# WirelessMonitorSch.net
KiCad netlist of a schematic drawn in Altium Designer
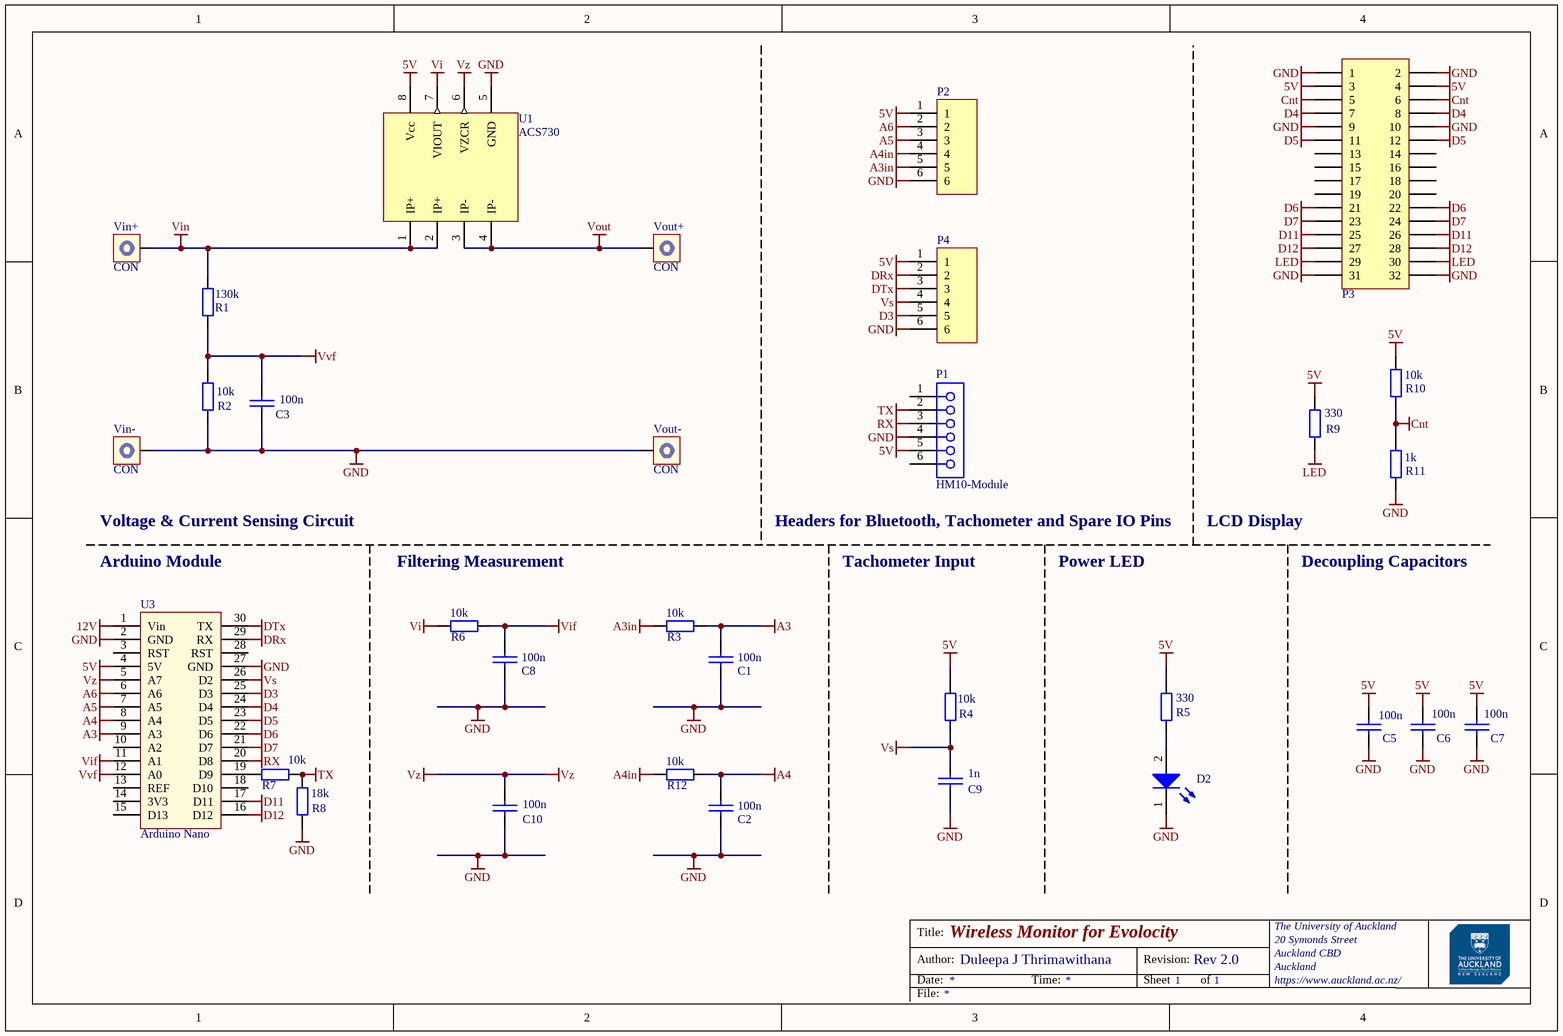
[diagram p0: WirelessMonitorSch.SchDoc]

(export (version "E")
  (design (tool "Eeschema 10.0.6"))
  (components
    (comp (ref "C1")
      (value "100n")
      (footprint "C0805")
      (description "CCAP0805")
      (fields (field (name "LCSC PART NUMBER") "C49678"))
      (libsource (lib "CommonDevices_V1") (part "CCAP0805"))
    )
    (comp (ref "C2")
      (value "100n")
      (footprint "C0805")
      (description "CCAP0805")
      (fields (field (name "LCSC PART NUMBER") "C49678"))
      (libsource (lib "CommonDevices_V1") (part "CCAP0805"))
    )
    (comp (ref "C3")
      (value "100n")
      (footprint "C0805")
      (description "CCAP0805")
      (fields (field (name "LCSC PART NUMBER") "C49678"))
      (libsource (lib "CommonDevices_V1") (part "CCAP0805"))
    )
    (comp (ref "C5")
      (value "100n")
      (footprint "C0805")
      (description "CCAP0805")
      (fields (field (name "LCSC PART NUMBER") "C49678"))
      (libsource (lib "CommonDevices_V1") (part "CCAP0805"))
    )
    (comp (ref "C6")
      (value "100n")
      (footprint "C0805")
      (description "CCAP0805")
      (fields (field (name "LCSC PART NUMBER") "C49678"))
      (libsource (lib "CommonDevices_V1") (part "CCAP0805"))
    )
    (comp (ref "C7")
      (value "100n")
      (footprint "C0805")
      (description "CCAP0805")
      (fields (field (name "LCSC PART NUMBER") "C49678"))
      (libsource (lib "CommonDevices_V1") (part "CCAP0805"))
    )
    (comp (ref "C8")
      (value "100n")
      (footprint "C0805")
      (description "CCAP0805")
      (fields (field (name "LCSC PART NUMBER") "C49678"))
      (libsource (lib "CommonDevices_V1") (part "CCAP0805"))
    )
    (comp (ref "C9")
      (value "1n")
      (footprint "C0805")
      (description "CCAP0805")
      (fields (field (name "LCSC PART NUMBER") "C46653"))
      (libsource (lib "CommonDevices_V1") (part "CCAP0805"))
    )
    (comp (ref "C10")
      (value "100n")
      (footprint "C0805")
      (description "CCAP0805")
      (fields (field (name "LCSC PART NUMBER") "C49678"))
      (libsource (lib "CommonDevices_V1") (part "CCAP0805"))
    )
    (comp (ref "D2")
      (value "LGR971-KN-1")
      (footprint "FP-LG_R971-MFG")
      (description "LED Uni-Color Green 572nm 2-Pin SMD T/R")
      (fields (field (name "LCSC PART NUMBER") "C2297"))
      (libsource (lib "ECSE@UoA") (part "8706943c75ba83719d021d2fdc84c58"))
    )
    (comp (ref "P1")
      (value "HM10-Module")
      (footprint "SMTC-SSW-106-02-X-S")
      (description "CONN RCPT 6POS 0.1 TIN PCB")
      (libsource (lib "ECSE@UoA") (part "SMTC-SSW-106-02-X-S-X"))
    )
    (comp (ref "P2")
      (value "Header 6X1")
      (footprint "HDR6X1_2P54")
      (description "Header, 6-Pin")
      (fields (field (name "PUBLISHER") "Altium Limited"))
      (libsource (lib "CommonDevices_V1") (part "HDR6X1"))
    )
    (comp (ref "P3")
      (value "HDR16X2")
      (footprint "HDR16X2_2P54")
      (description "Header, 16-Pin, Dual row")
      (libsource (lib "CommonDevices_V1") (part "HDR16X2"))
    )
    (comp (ref "P4")
      (value "Header 6X1")
      (footprint "HDR6X1_2P54")
      (description "Header, 6-Pin")
      (fields (field (name "PUBLISHER") "Altium Limited"))
      (libsource (lib "CommonDevices_V1") (part "HDR6X1"))
    )
    (comp (ref "R1")
      (value "130k")
      (footprint "R0805")
      (description "RES0805")
      (fields (field (name "LCSC PART NUMBER") "C25617"))
      (libsource (lib "") (part "RES0805_1"))
    )
    (comp (ref "R2")
      (value "10k")
      (footprint "R0805")
      (description "RES0805")
      (fields (field (name "LCSC PART NUMBER") "C17414"))
      (libsource (lib "") (part "RES0805_1"))
    )
    (comp (ref "R3")
      (value "10k")
      (footprint "R0805")
      (description "RES0805")
      (fields (field (name "LCSC PART NUMBER") "C17414"))
      (libsource (lib "CommonDevices_V1") (part "RES0805"))
    )
    (comp (ref "R4")
      (value "10k")
      (footprint "R0805")
      (description "RES0805")
      (fields (field (name "LCSC PART NUMBER") "C17414"))
      (libsource (lib "") (part "RES0805_1"))
    )
    (comp (ref "R5")
      (value "330")
      (footprint "R0805")
      (description "RES0805")
      (fields (field (name "LCSC PART NUMBER") "C17630"))
      (libsource (lib "") (part "RES0805_1"))
    )
    (comp (ref "R6")
      (value "10k")
      (footprint "R0805")
      (description "RES0805")
      (fields (field (name "LCSC PART NUMBER") "C17414"))
      (libsource (lib "CommonDevices_V1") (part "RES0805"))
    )
    (comp (ref "R7")
      (value "10k")
      (footprint "R0805")
      (description "RES0805")
      (fields (field (name "LCSC PART NUMBER") "C17414"))
      (libsource (lib "CommonDevices_V1") (part "RES0805"))
    )
    (comp (ref "R8")
      (value "18k")
      (footprint "R0805")
      (description "RES0805")
      (fields (field (name "LCSC PART NUMBER") "C17506"))
      (libsource (lib "") (part "RES0805_1"))
    )
    (comp (ref "R9")
      (value "330")
      (footprint "R0805")
      (description "RES0805")
      (fields (field (name "LCSC PART NUMBER") "C17630"))
      (libsource (lib "") (part "RES0805_1"))
    )
    (comp (ref "R10")
      (value "10k")
      (footprint "R0805")
      (description "RES0805")
      (fields (field (name "LCSC PART NUMBER") "C17414"))
      (libsource (lib "") (part "RES0805_1"))
    )
    (comp (ref "R11")
      (value "1k")
      (footprint "R0805")
      (description "RES0805")
      (fields (field (name "LCSC PART NUMBER") "C17513"))
      (libsource (lib "") (part "RES0805_1"))
    )
    (comp (ref "R12")
      (value "10k")
      (footprint "R0805")
      (description "RES0805")
      (fields (field (name "LCSC PART NUMBER") "C17414"))
      (libsource (lib "CommonDevices_V1") (part "RES0805"))
    )
    (comp (ref "U1")
      (value "ACS730")
      (footprint "SOIC8")
      (libsource (lib "CommonDevices_V1") (part "ACS730"))
    )
    (comp (ref "U3")
      (value "Arduino Nano")
      (footprint "ArduinoNanoSMT")
      (libsource (lib "CommonDevices_V1") (part "ArduinoNano"))
    )
    (comp (ref "Vin+")
      (value "CON")
      (footprint "CON_M3")
      (description "Term")
      (fields (field (name "PART NUMBER") "74651194R") (field (name "PUBLISHER") "Wurth Elektronik"))
      (libsource (lib "") (part "Connector_1"))
    )
    (comp (ref "Vin-")
      (value "CON")
      (footprint "CON_M3")
      (description "Term")
      (fields (field (name "PART NUMBER") "74651194R") (field (name "PUBLISHER") "Wurth Elektronik"))
      (libsource (lib "") (part "Connector_1"))
    )
    (comp (ref "Vout+")
      (value "CON")
      (footprint "CON_M3")
      (description "Term")
      (fields (field (name "PART NUMBER") "74651194R") (field (name "PUBLISHER") "Wurth Elektronik"))
      (libsource (lib "CommonDevices_V1") (part "Connector"))
    )
    (comp (ref "Vout-")
      (value "CON")
      (footprint "CON_M3")
      (description "Term")
      (fields (field (name "PART NUMBER") "74651194R") (field (name "PUBLISHER") "Wurth Elektronik"))
      (libsource (lib "CommonDevices_V1") (part "Connector"))
    )
  )
  (nets
    (net (code "1") (name "5V") (class "Default")
      (node (ref "C5") (pin "2") (pinfunction "2_2") (pintype "passive"))
      (node (ref "C6") (pin "2") (pinfunction "2_2") (pintype "passive"))
      (node (ref "C7") (pin "2") (pinfunction "2_2") (pintype "passive"))
      (node (ref "P1") (pin "5") (pinfunction "5_5") (pintype "passive"))
      (node (ref "P2") (pin "1") (pinfunction "1_1") (pintype "passive"))
      (node (ref "P3") (pin "3") (pinfunction "3_3") (pintype "passive"))
      (node (ref "P3") (pin "4") (pinfunction "4_4") (pintype "passive"))
      (node (ref "P4") (pin "1") (pinfunction "1_1") (pintype "passive"))
      (node (ref "R10") (pin "2") (pinfunction "2_2") (pintype "passive"))
      (node (ref "R4") (pin "2") (pinfunction "2_2") (pintype "passive"))
      (node (ref "R5") (pin "2") (pinfunction "2_2") (pintype "passive"))
      (node (ref "R9") (pin "2") (pinfunction "2_2") (pintype "passive"))
      (node (ref "U1") (pin "8") (pinfunction "Vcc_8") (pintype "power_in"))
      (node (ref "U3") (pin "4") (pinfunction "5V_4") (pintype "passive"))
    )
    (net (code "2") (name "12V") (class "Default")
      (node (ref "U3") (pin "1") (pinfunction "Vin_1") (pintype "passive"))
    )
    (net (code "3") (name "A3") (class "Default")
      (node (ref "C1") (pin "2") (pinfunction "2_2") (pintype "passive"))
      (node (ref "R3") (pin "1") (pinfunction "1_1") (pintype "passive"))
      (node (ref "U3") (pin "9") (pinfunction "A3_9") (pintype "passive"))
    )
    (net (code "4") (name "A3in") (class "Default")
      (node (ref "P2") (pin "5") (pinfunction "5_5") (pintype "passive"))
      (node (ref "R3") (pin "2") (pinfunction "2_2") (pintype "passive"))
    )
    (net (code "5") (name "A4") (class "Default")
      (node (ref "C2") (pin "2") (pinfunction "2_2") (pintype "passive"))
      (node (ref "R12") (pin "1") (pinfunction "1_1") (pintype "passive"))
      (node (ref "U3") (pin "8") (pinfunction "A4_8") (pintype "passive"))
    )
    (net (code "6") (name "A4in") (class "Default")
      (node (ref "P2") (pin "4") (pinfunction "4_4") (pintype "passive"))
      (node (ref "R12") (pin "2") (pinfunction "2_2") (pintype "passive"))
    )
    (net (code "7") (name "A5") (class "Default")
      (node (ref "P2") (pin "3") (pinfunction "3_3") (pintype "passive"))
      (node (ref "U3") (pin "7") (pinfunction "A5_7") (pintype "passive"))
    )
    (net (code "8") (name "A6") (class "Default")
      (node (ref "P2") (pin "2") (pinfunction "2_2") (pintype "passive"))
      (node (ref "U3") (pin "6") (pinfunction "A6_6") (pintype "passive"))
    )
    (net (code "9") (name "Cnt") (class "Default")
      (node (ref "P3") (pin "5") (pinfunction "5_5") (pintype "passive"))
      (node (ref "P3") (pin "6") (pinfunction "6_6") (pintype "passive"))
      (node (ref "R10") (pin "1") (pinfunction "1_1") (pintype "passive"))
      (node (ref "R11") (pin "2") (pinfunction "2_2") (pintype "passive"))
    )
    (net (code "10") (name "D3") (class "Default")
      (node (ref "P4") (pin "5") (pinfunction "5_5") (pintype "passive"))
      (node (ref "U3") (pin "25") (pinfunction "D3_25") (pintype "passive"))
    )
    (net (code "11") (name "D4") (class "Default")
      (node (ref "P3") (pin "7") (pinfunction "7_7") (pintype "passive"))
      (node (ref "P3") (pin "8") (pinfunction "8_8") (pintype "passive"))
      (node (ref "U3") (pin "24") (pinfunction "D4_24") (pintype "passive"))
    )
    (net (code "12") (name "D5") (class "Default")
      (node (ref "P3") (pin "11") (pinfunction "11_11") (pintype "passive"))
      (node (ref "P3") (pin "12") (pinfunction "12_12") (pintype "passive"))
      (node (ref "U3") (pin "23") (pinfunction "D5_23") (pintype "passive"))
    )
    (net (code "13") (name "D6") (class "Default")
      (node (ref "P3") (pin "21") (pinfunction "21_21") (pintype "passive"))
      (node (ref "P3") (pin "22") (pinfunction "22_22") (pintype "passive"))
      (node (ref "U3") (pin "22") (pinfunction "D6_22") (pintype "passive"))
    )
    (net (code "14") (name "D7") (class "Default")
      (node (ref "P3") (pin "23") (pinfunction "23_23") (pintype "passive"))
      (node (ref "P3") (pin "24") (pinfunction "24_24") (pintype "passive"))
      (node (ref "U3") (pin "21") (pinfunction "D7_21") (pintype "passive"))
    )
    (net (code "15") (name "D11") (class "Default")
      (node (ref "P3") (pin "25") (pinfunction "25_25") (pintype "passive"))
      (node (ref "P3") (pin "26") (pinfunction "26_26") (pintype "passive"))
      (node (ref "U3") (pin "17") (pinfunction "D11_17") (pintype "passive"))
    )
    (net (code "16") (name "D12") (class "Default")
      (node (ref "P3") (pin "27") (pinfunction "27_27") (pintype "passive"))
      (node (ref "P3") (pin "28") (pinfunction "28_28") (pintype "passive"))
      (node (ref "U3") (pin "16") (pinfunction "D12_16") (pintype "passive"))
    )
    (net (code "17") (name "DRx") (class "Default")
      (node (ref "P4") (pin "2") (pinfunction "2_2") (pintype "passive"))
      (node (ref "U3") (pin "29") (pinfunction "RX_29") (pintype "passive"))
    )
    (net (code "18") (name "DTx") (class "Default")
      (node (ref "P4") (pin "3") (pinfunction "3_3") (pintype "passive"))
      (node (ref "U3") (pin "30") (pinfunction "TX_30") (pintype "passive"))
    )
    (net (code "19") (name "GND") (class "Default")
      (node (ref "C1") (pin "1") (pinfunction "1_1") (pintype "passive"))
      (node (ref "C10") (pin "1") (pinfunction "1_1") (pintype "passive"))
      (node (ref "C2") (pin "1") (pinfunction "1_1") (pintype "passive"))
      (node (ref "C3") (pin "1") (pinfunction "1_1") (pintype "passive"))
      (node (ref "C5") (pin "1") (pinfunction "1_1") (pintype "passive"))
      (node (ref "C6") (pin "1") (pinfunction "1_1") (pintype "passive"))
      (node (ref "C7") (pin "1") (pinfunction "1_1") (pintype "passive"))
      (node (ref "C8") (pin "1") (pinfunction "1_1") (pintype "passive"))
      (node (ref "C9") (pin "1") (pinfunction "1_1") (pintype "passive"))
      (node (ref "D2") (pin "1") (pinfunction "C_1") (pintype "passive"))
      (node (ref "P1") (pin "4") (pinfunction "4_4") (pintype "passive"))
      (node (ref "P2") (pin "6") (pinfunction "6_6") (pintype "passive"))
      (node (ref "P3") (pin "1") (pinfunction "1_1") (pintype "passive"))
      (node (ref "P3") (pin "10") (pinfunction "10_10") (pintype "passive"))
      (node (ref "P3") (pin "2") (pinfunction "2_2") (pintype "passive"))
      (node (ref "P3") (pin "31") (pinfunction "31_31") (pintype "passive"))
      (node (ref "P3") (pin "32") (pinfunction "32_32") (pintype "passive"))
      (node (ref "P3") (pin "9") (pinfunction "9_9") (pintype "passive"))
      (node (ref "P4") (pin "6") (pinfunction "6_6") (pintype "passive"))
      (node (ref "R11") (pin "1") (pinfunction "1_1") (pintype "passive"))
      (node (ref "R2") (pin "1") (pinfunction "1_1") (pintype "passive"))
      (node (ref "R8") (pin "1") (pinfunction "1_1") (pintype "passive"))
      (node (ref "U1") (pin "5") (pinfunction "GND_5") (pintype "power_in"))
      (node (ref "U3") (pin "2") (pinfunction "GND_2") (pintype "passive"))
      (node (ref "U3") (pin "27") (pinfunction "GND_27") (pintype "passive"))
      (node (ref "Vin-") (pin "1") (pinfunction "1_1") (pintype "passive"))
      (node (ref "Vout-") (pin "1") (pinfunction "1_1") (pintype "passive"))
    )
    (net (code "20") (name "LED") (class "Default")
      (node (ref "P3") (pin "29") (pinfunction "29_29") (pintype "passive"))
      (node (ref "P3") (pin "30") (pinfunction "30_30") (pintype "passive"))
      (node (ref "R9") (pin "1") (pinfunction "1_1") (pintype "passive"))
    )
    (net (code "21") (name "Net-(D2-A)") (class "Default")
      (node (ref "D2") (pin "2") (pinfunction "A_2") (pintype "passive"))
      (node (ref "R5") (pin "1") (pinfunction "1_1") (pintype "passive"))
    )
    (net (code "22") (name "Net-(U3-D9)") (class "Default")
      (node (ref "R7") (pin "2") (pinfunction "2_2") (pintype "passive"))
      (node (ref "U3") (pin "19") (pinfunction "D9_19") (pintype "passive"))
    )
    (net (code "23") (name "RX") (class "Default")
      (node (ref "P1") (pin "3") (pinfunction "3_3") (pintype "passive"))
      (node (ref "U3") (pin "20") (pinfunction "D8_20") (pintype "passive"))
    )
    (net (code "24") (name "TX") (class "Default")
      (node (ref "P1") (pin "2") (pinfunction "2_2") (pintype "passive"))
      (node (ref "R7") (pin "1") (pinfunction "1_1") (pintype "passive"))
      (node (ref "R8") (pin "2") (pinfunction "2_2") (pintype "passive"))
    )
    (net (code "25") (name "Vi") (class "Default")
      (node (ref "R6") (pin "2") (pinfunction "2_2") (pintype "passive"))
      (node (ref "U1") (pin "7") (pinfunction "VIOUT_7") (pintype "output"))
    )
    (net (code "26") (name "Vif") (class "Default")
      (node (ref "C8") (pin "2") (pinfunction "2_2") (pintype "passive"))
      (node (ref "R6") (pin "1") (pinfunction "1_1") (pintype "passive"))
      (node (ref "U3") (pin "11") (pinfunction "A1_11") (pintype "passive"))
    )
    (net (code "27") (name "Vin") (class "Default")
      (node (ref "R1") (pin "2") (pinfunction "2_2") (pintype "passive"))
      (node (ref "U1") (pin "1") (pinfunction "IP+_1") (pintype "passive"))
      (node (ref "U1") (pin "2") (pinfunction "IP+_2") (pintype "power_in"))
      (node (ref "Vin+") (pin "1") (pinfunction "1_1") (pintype "passive"))
    )
    (net (code "28") (name "Vout") (class "Default")
      (node (ref "U1") (pin "3") (pinfunction "IP-_3") (pintype "power_in"))
      (node (ref "U1") (pin "4") (pinfunction "IP-_4") (pintype "passive"))
      (node (ref "Vout+") (pin "1") (pinfunction "1_1") (pintype "passive"))
    )
    (net (code "29") (name "Vs") (class "Default")
      (node (ref "C9") (pin "2") (pinfunction "2_2") (pintype "passive"))
      (node (ref "P4") (pin "4") (pinfunction "4_4") (pintype "passive"))
      (node (ref "R4") (pin "1") (pinfunction "1_1") (pintype "passive"))
      (node (ref "U3") (pin "26") (pinfunction "D2_26") (pintype "passive"))
    )
    (net (code "30") (name "Vvf") (class "Default")
      (node (ref "C3") (pin "2") (pinfunction "2_2") (pintype "passive"))
      (node (ref "R1") (pin "1") (pinfunction "1_1") (pintype "passive"))
      (node (ref "R2") (pin "2") (pinfunction "2_2") (pintype "passive"))
      (node (ref "U3") (pin "12") (pinfunction "A0_12") (pintype "passive"))
    )
    (net (code "31") (name "Vz") (class "Default")
      (node (ref "C10") (pin "2") (pinfunction "2_2") (pintype "passive"))
      (node (ref "U1") (pin "6") (pinfunction "VZCR_6") (pintype "output"))
      (node (ref "U3") (pin "5") (pinfunction "A7_5") (pintype "passive"))
    )
    (net (code "32") (name "unconnected-(P1-Pad1)") (class "Default")
      (node (ref "P1") (pin "1") (pinfunction "1_1") (pintype "passive"))
    )
    (net (code "33") (name "unconnected-(P1-Pad6)") (class "Default")
      (node (ref "P1") (pin "6") (pinfunction "6_6") (pintype "passive"))
    )
    (net (code "34") (name "unconnected-(P3-Pad13)") (class "Default")
      (node (ref "P3") (pin "13") (pinfunction "13_13") (pintype "passive"))
    )
    (net (code "35") (name "unconnected-(P3-Pad14)") (class "Default")
      (node (ref "P3") (pin "14") (pinfunction "14_14") (pintype "passive"))
    )
    (net (code "36") (name "unconnected-(P3-Pad15)") (class "Default")
      (node (ref "P3") (pin "15") (pinfunction "15_15") (pintype "passive"))
    )
    (net (code "37") (name "unconnected-(P3-Pad16)") (class "Default")
      (node (ref "P3") (pin "16") (pinfunction "16_16") (pintype "passive"))
    )
    (net (code "38") (name "unconnected-(P3-Pad17)") (class "Default")
      (node (ref "P3") (pin "17") (pinfunction "17_17") (pintype "passive"))
    )
    (net (code "39") (name "unconnected-(P3-Pad18)") (class "Default")
      (node (ref "P3") (pin "18") (pinfunction "18_18") (pintype "passive"))
    )
    (net (code "40") (name "unconnected-(P3-Pad19)") (class "Default")
      (node (ref "P3") (pin "19") (pinfunction "19_19") (pintype "passive"))
    )
    (net (code "41") (name "unconnected-(P3-Pad20)") (class "Default")
      (node (ref "P3") (pin "20") (pinfunction "20_20") (pintype "passive"))
    )
    (net (code "42") (name "unconnected-(U3-3V3-Pad14)") (class "Default")
      (node (ref "U3") (pin "14") (pinfunction "3V3_14") (pintype "passive"))
    )
    (net (code "43") (name "unconnected-(U3-A2-Pad10)") (class "Default")
      (node (ref "U3") (pin "10") (pinfunction "A2_10") (pintype "passive"))
    )
    (net (code "44") (name "unconnected-(U3-D10-Pad18)") (class "Default")
      (node (ref "U3") (pin "18") (pinfunction "D10_18") (pintype "passive"))
    )
    (net (code "45") (name "unconnected-(U3-D13-Pad15)") (class "Default")
      (node (ref "U3") (pin "15") (pinfunction "D13_15") (pintype "passive"))
    )
    (net (code "46") (name "unconnected-(U3-REF-Pad13)") (class "Default")
      (node (ref "U3") (pin "13") (pinfunction "REF_13") (pintype "passive"))
    )
    (net (code "47") (name "unconnected-(U3-RST-Pad3)") (class "Default")
      (node (ref "U3") (pin "3") (pinfunction "RST_3") (pintype "passive"))
    )
    (net (code "48") (name "unconnected-(U3-RST-Pad28)") (class "Default")
      (node (ref "U3") (pin "28") (pinfunction "RST_28") (pintype "passive"))
    )
  )
)
